# main.net
KiCad netlist of a schematic drawn in EAGLE
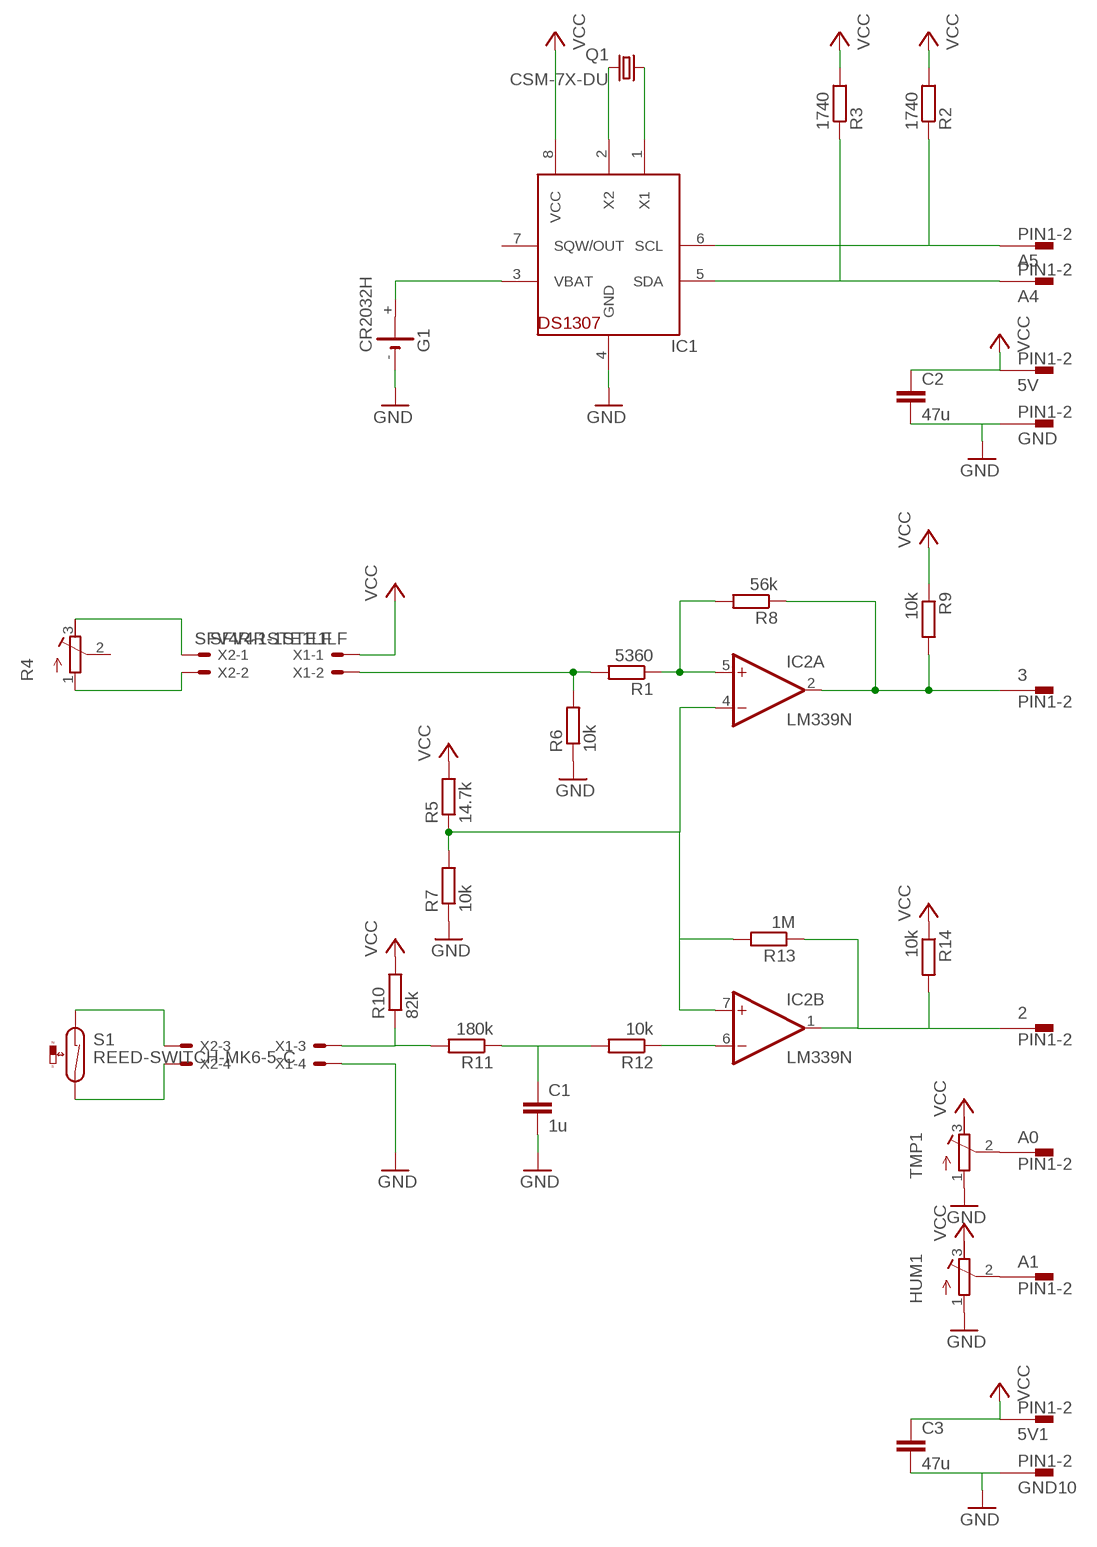
[diagram p0: schematic, sheet 1]

(export (version "E")
  (design (tool "Eeschema 10.0.6"))
  (components
    (comp (ref "2")
      (value "PIN1-2")
      (footprint "eagle-import:62221")
      (fields (field (name "MF") "TYCO ELECTRONICS") (field (name "MPN") "62221-1"))
      (libsource (lib "eagle-import") (part "PIN1-2"))
    )
    (comp (ref "3")
      (value "PIN1-2")
      (footprint "eagle-import:62221")
      (fields (field (name "MF") "TYCO ELECTRONICS") (field (name "MPN") "62221-1"))
      (libsource (lib "eagle-import") (part "PIN1-2"))
    )
    (comp (ref "5V")
      (value "PIN1-2")
      (footprint "eagle-import:62221")
      (fields (field (name "MF") "TYCO ELECTRONICS") (field (name "MPN") "62221-1"))
      (libsource (lib "eagle-import") (part "PIN1-2"))
    )
    (comp (ref "5V1")
      (value "PIN1-2")
      (footprint "eagle-import:62221")
      (fields (field (name "MF") "TYCO ELECTRONICS") (field (name "MPN") "62221-1"))
      (libsource (lib "eagle-import") (part "PIN1-2"))
    )
    (comp (ref "A0")
      (value "PIN1-2")
      (footprint "eagle-import:62221")
      (fields (field (name "MF") "TYCO ELECTRONICS") (field (name "MPN") "62221-1"))
      (libsource (lib "eagle-import") (part "PIN1-2"))
    )
    (comp (ref "A1")
      (value "PIN1-2")
      (footprint "eagle-import:62221")
      (fields (field (name "MF") "TYCO ELECTRONICS") (field (name "MPN") "62221-1"))
      (libsource (lib "eagle-import") (part "PIN1-2"))
    )
    (comp (ref "A4")
      (value "PIN1-2")
      (footprint "eagle-import:62221")
      (fields (field (name "MF") "TYCO ELECTRONICS") (field (name "MPN") "62221-1"))
      (libsource (lib "eagle-import") (part "PIN1-2"))
    )
    (comp (ref "A5")
      (value "PIN1-2")
      (footprint "eagle-import:62221")
      (fields (field (name "MF") "TYCO ELECTRONICS") (field (name "MPN") "62221-1"))
      (libsource (lib "eagle-import") (part "PIN1-2"))
    )
    (comp (ref "C1")
      (value "1u")
      (footprint "eagle-import:C2.5-3")
      (libsource (lib "eagle-import") (part "C2,5-3"))
    )
    (comp (ref "C2")
      (value "47u")
      (footprint "eagle-import:C2.5-3")
      (libsource (lib "eagle-import") (part "C2,5-3"))
    )
    (comp (ref "C3")
      (value "47u")
      (footprint "eagle-import:C2.5-3")
      (libsource (lib "eagle-import") (part "C2,5-3"))
    )
    (comp (ref "G1")
      (value "CR2032H")
      (footprint "eagle-import:CR2032H")
      (libsource (lib "eagle-import") (part "CR2032H"))
    )
    (comp (ref "GND")
      (value "PIN1-2")
      (footprint "eagle-import:62221")
      (fields (field (name "MF") "TYCO ELECTRONICS") (field (name "MPN") "62221-1"))
      (libsource (lib "eagle-import") (part "PIN1-2"))
    )
    (comp (ref "GND10")
      (value "PIN1-2")
      (footprint "eagle-import:62221")
      (fields (field (name "MF") "TYCO ELECTRONICS") (field (name "MPN") "62221-1"))
      (libsource (lib "eagle-import") (part "PIN1-2"))
    )
    (comp (ref "HUM1")
      (value "R-TRIMM4G/J")
      (footprint "eagle-import:RTRIM4G_J")
      (libsource (lib "eagle-import") (part "R-TRIMM4G/J"))
    )
    (comp (ref "IC1")
      (value "DS1307")
      (footprint "eagle-import:DIL08")
      (libsource (lib "eagle-import") (part "DS1307"))
    )
    (comp (ref "IC2")
      (value "LM339N")
      (footprint "eagle-import:DIL14")
      (libsource (lib "eagle-import") (part "LM339N"))
    )
    (comp (ref "Q1")
      (value "CSM-7X-DU")
      (footprint "eagle-import:CSM-7X-DU")
      (libsource (lib "eagle-import") (part "CSM-7X-DU"))
    )
    (comp (ref "R1")
      (value "5360")
      (footprint "eagle-import:0204V")
      (libsource (lib "eagle-import") (part "R-EU_0204/2V"))
    )
    (comp (ref "R2")
      (value "1740")
      (footprint "eagle-import:0204V")
      (libsource (lib "eagle-import") (part "R-EU_0204/2V"))
    )
    (comp (ref "R3")
      (value "1740")
      (footprint "eagle-import:0204V")
      (libsource (lib "eagle-import") (part "R-EU_0204/2V"))
    )
    (comp (ref "R4")
      (value "R-TRIMM4G/J")
      (footprint "eagle-import:RTRIM4G_J")
      (libsource (lib "eagle-import") (part "R-TRIMM4G/J"))
    )
    (comp (ref "R5")
      (value "14.7k")
      (footprint "eagle-import:0204V")
      (libsource (lib "eagle-import") (part "R-EU_0204/2V"))
    )
    (comp (ref "R6")
      (value "10k")
      (footprint "eagle-import:0204V")
      (libsource (lib "eagle-import") (part "R-EU_0204/2V"))
    )
    (comp (ref "R7")
      (value "10k")
      (footprint "eagle-import:0204V")
      (libsource (lib "eagle-import") (part "R-EU_0204/2V"))
    )
    (comp (ref "R8")
      (value "56k")
      (footprint "eagle-import:0204V")
      (libsource (lib "eagle-import") (part "R-EU_0204/2V"))
    )
    (comp (ref "R9")
      (value "10k")
      (footprint "eagle-import:0204V")
      (libsource (lib "eagle-import") (part "R-EU_0204/2V"))
    )
    (comp (ref "R10")
      (value "82k")
      (footprint "eagle-import:0204V")
      (libsource (lib "eagle-import") (part "R-EU_0204/2V"))
    )
    (comp (ref "R11")
      (value "180k")
      (footprint "eagle-import:0204V")
      (libsource (lib "eagle-import") (part "R-EU_0204/2V"))
    )
    (comp (ref "R12")
      (value "10k")
      (footprint "eagle-import:0204V")
      (libsource (lib "eagle-import") (part "R-EU_0204/2V"))
    )
    (comp (ref "R13")
      (value "1M")
      (footprint "eagle-import:0204V")
      (libsource (lib "eagle-import") (part "R-EU_0204/2V"))
    )
    (comp (ref "R14")
      (value "10k")
      (footprint "eagle-import:0204V")
      (libsource (lib "eagle-import") (part "R-EU_0204/2V"))
    )
    (comp (ref "S1")
      (value "REED-SWITCH-MK6-5-C")
      (footprint "eagle-import:MK6-5")
      (fields (field (name "MF") "MEDER") (field (name "MPN") "MK6-5-C"))
      (libsource (lib "eagle-import") (part "REED-SWITCH-MK6-5-C"))
    )
    (comp (ref "TMP1")
      (value "R-TRIMM4G/J")
      (footprint "eagle-import:RTRIM4G_J")
      (libsource (lib "eagle-import") (part "R-TRIMM4G/J"))
    )
    (comp (ref "X1")
      (value "SFV4R-1STE1LF")
      (footprint "eagle-import:SFV4R-1STE1LF")
      (libsource (lib "eagle-import") (part "SFV4R-1STE1LF"))
    )
    (comp (ref "X2")
      (value "SFV4R-1STE1LF")
      (footprint "eagle-import:SFV4R-1STE1LF")
      (libsource (lib "eagle-import") (part "SFV4R-1STE1LF"))
    )
  )
  (nets
    (net (code "1") (name "GND") (class "Default")
      (node (ref "C1") (pin "2") (pinfunction "2_2") (pintype "passive"))
      (node (ref "C2") (pin "2") (pinfunction "2_2") (pintype "passive"))
      (node (ref "C3") (pin "2") (pinfunction "2_2") (pintype "passive"))
      (node (ref "G1") (pin "-") (pinfunction "-_-") (pintype "passive"))
      (node (ref "GND") (pin "1") (pinfunction "1_1") (pintype "passive"))
      (node (ref "GND10") (pin "1") (pinfunction "1_1") (pintype "passive"))
      (node (ref "HUM1") (pin "1") (pinfunction "A_1") (pintype "passive"))
      (node (ref "IC1") (pin "4") (pinfunction "GND_4") (pintype "power_in"))
      (node (ref "R6") (pin "1") (pinfunction "1_1") (pintype "passive"))
      (node (ref "R7") (pin "1") (pinfunction "1_1") (pintype "passive"))
      (node (ref "TMP1") (pin "1") (pinfunction "A_1") (pintype "passive"))
      (node (ref "X1") (pin "4") (pinfunction "S_4") (pintype "passive"))
    )
    (net (code "2") (name "Net-(C1-Pad1)") (class "Default")
      (node (ref "C1") (pin "1") (pinfunction "1_1") (pintype "passive"))
      (node (ref "R11") (pin "1") (pinfunction "1_1") (pintype "passive"))
      (node (ref "R12") (pin "2") (pinfunction "2_2") (pintype "passive"))
    )
    (net (code "3") (name "Net-(HUM1-S)") (class "Default")
      (node (ref "A1") (pin "1") (pinfunction "1_1") (pintype "passive"))
      (node (ref "HUM1") (pin "2") (pinfunction "S_2") (pintype "passive"))
    )
    (net (code "4") (name "Net-(IC1-SCL)") (class "Default")
      (node (ref "A5") (pin "1") (pinfunction "1_1") (pintype "passive"))
      (node (ref "IC1") (pin "6") (pinfunction "SCL_6") (pintype "bidirectional"))
      (node (ref "R2") (pin "1") (pinfunction "1_1") (pintype "passive"))
    )
    (net (code "5") (name "Net-(IC1-SDA)") (class "Default")
      (node (ref "A4") (pin "1") (pinfunction "1_1") (pintype "passive"))
      (node (ref "IC1") (pin "5") (pinfunction "SDA_5") (pintype "bidirectional"))
      (node (ref "R3") (pin "1") (pinfunction "1_1") (pintype "passive"))
    )
    (net (code "6") (name "Net-(IC1-VBAT)") (class "Default")
      (node (ref "G1") (pin "+") (pinfunction "+_+") (pintype "passive"))
      (node (ref "IC1") (pin "3") (pinfunction "VBAT_3") (pintype "power_in"))
    )
    (net (code "7") (name "Net-(IC1-X1)") (class "Default")
      (node (ref "IC1") (pin "1") (pinfunction "X1_1") (pintype "passive"))
      (node (ref "Q1") (pin "1") (pinfunction "1_1") (pintype "passive"))
    )
    (net (code "8") (name "Net-(IC1-X2)") (class "Default")
      (node (ref "IC1") (pin "2") (pinfunction "X2_2") (pintype "passive"))
      (node (ref "Q1") (pin "2") (pinfunction "2_2") (pintype "passive"))
    )
    (net (code "9") (name "Net-(IC2A-+IN)") (class "Default")
      (node (ref "IC2") (pin "5") (pinfunction "+IN_5") (pintype "input"))
      (node (ref "R1") (pin "1") (pinfunction "1_1") (pintype "passive"))
      (node (ref "R8") (pin "2") (pinfunction "2_2") (pintype "passive"))
    )
    (net (code "10") (name "Net-(IC2A--IN)") (class "Default")
      (node (ref "IC2") (pin "4") (pinfunction "-IN_4") (pintype "input"))
      (node (ref "IC2") (pin "7") (pinfunction "+IN_7") (pintype "input"))
      (node (ref "R13") (pin "2") (pinfunction "2_2") (pintype "passive"))
      (node (ref "R5") (pin "1") (pinfunction "1_1") (pintype "passive"))
      (node (ref "R7") (pin "2") (pinfunction "2_2") (pintype "passive"))
    )
    (net (code "11") (name "Net-(IC2A-OUT)") (class "Default")
      (node (ref "3") (pin "1") (pinfunction "1_1") (pintype "passive"))
      (node (ref "IC2") (pin "2") (pinfunction "OUT_2") (pintype "open_collector"))
      (node (ref "R8") (pin "1") (pinfunction "1_1") (pintype "passive"))
      (node (ref "R9") (pin "2") (pinfunction "2_2") (pintype "passive"))
    )
    (net (code "12") (name "Net-(IC2B--IN)") (class "Default")
      (node (ref "IC2") (pin "6") (pinfunction "-IN_6") (pintype "input"))
      (node (ref "R12") (pin "1") (pinfunction "1_1") (pintype "passive"))
    )
    (net (code "13") (name "Net-(IC2B-OUT)") (class "Default")
      (node (ref "2") (pin "1") (pinfunction "1_1") (pintype "passive"))
      (node (ref "IC2") (pin "1") (pinfunction "OUT_1") (pintype "open_collector"))
      (node (ref "R13") (pin "1") (pinfunction "1_1") (pintype "passive"))
      (node (ref "R14") (pin "2") (pinfunction "2_2") (pintype "passive"))
    )
    (net (code "14") (name "Net-(R4-A)") (class "Default")
      (node (ref "R4") (pin "1") (pinfunction "A_1") (pintype "passive"))
      (node (ref "X2") (pin "2") (pinfunction "S_2") (pintype "passive"))
    )
    (net (code "15") (name "Net-(R4-E)") (class "Default")
      (node (ref "R4") (pin "3") (pinfunction "E_3") (pintype "passive"))
      (node (ref "X2") (pin "1") (pinfunction "S_1") (pintype "passive"))
    )
    (net (code "16") (name "Net-(TMP1-S)") (class "Default")
      (node (ref "A0") (pin "1") (pinfunction "1_1") (pintype "passive"))
      (node (ref "TMP1") (pin "2") (pinfunction "S_2") (pintype "passive"))
    )
    (net (code "17") (name "Net-(X1B-S)") (class "Default")
      (node (ref "R1") (pin "2") (pinfunction "2_2") (pintype "passive"))
      (node (ref "R6") (pin "2") (pinfunction "2_2") (pintype "passive"))
      (node (ref "X1") (pin "2") (pinfunction "S_2") (pintype "passive"))
    )
    (net (code "18") (name "Net-(X1C-S)") (class "Default")
      (node (ref "R10") (pin "1") (pinfunction "1_1") (pintype "passive"))
      (node (ref "R11") (pin "2") (pinfunction "2_2") (pintype "passive"))
      (node (ref "X1") (pin "3") (pinfunction "S_3") (pintype "passive"))
    )
    (net (code "19") (name "Net-(X2C-S)") (class "Default")
      (node (ref "S1") (pin "1") (pinfunction "1_1") (pintype "passive"))
      (node (ref "X2") (pin "3") (pinfunction "S_3") (pintype "passive"))
    )
    (net (code "20") (name "Net-(X2D-S)") (class "Default")
      (node (ref "S1") (pin "2") (pinfunction "2_2") (pintype "passive"))
      (node (ref "X2") (pin "4") (pinfunction "S_4") (pintype "passive"))
    )
    (net (code "21") (name "VCC") (class "Default")
      (node (ref "5V") (pin "1") (pinfunction "1_1") (pintype "passive"))
      (node (ref "5V1") (pin "1") (pinfunction "1_1") (pintype "passive"))
      (node (ref "C2") (pin "1") (pinfunction "1_1") (pintype "passive"))
      (node (ref "C3") (pin "1") (pinfunction "1_1") (pintype "passive"))
      (node (ref "HUM1") (pin "3") (pinfunction "E_3") (pintype "passive"))
      (node (ref "IC1") (pin "8") (pinfunction "VCC_8") (pintype "power_in"))
      (node (ref "R10") (pin "2") (pinfunction "2_2") (pintype "passive"))
      (node (ref "R14") (pin "1") (pinfunction "1_1") (pintype "passive"))
      (node (ref "R2") (pin "2") (pinfunction "2_2") (pintype "passive"))
      (node (ref "R3") (pin "2") (pinfunction "2_2") (pintype "passive"))
      (node (ref "R5") (pin "2") (pinfunction "2_2") (pintype "passive"))
      (node (ref "R9") (pin "1") (pinfunction "1_1") (pintype "passive"))
      (node (ref "TMP1") (pin "3") (pinfunction "E_3") (pintype "passive"))
      (node (ref "X1") (pin "1") (pinfunction "S_1") (pintype "passive"))
    )
    (net (code "22") (name "unconnected-(G1-+-Pad+@1)") (class "Default")
      (node (ref "G1") (pin "+@1") (pinfunction "+_+@1") (pintype "passive"))
    )
    (net (code "23") (name "unconnected-(IC1-SQW{slash}OUT-Pad7)") (class "Default")
      (node (ref "IC1") (pin "7") (pinfunction "SQW/OUT_7") (pintype "bidirectional"))
    )
    (net (code "24") (name "unconnected-(R4-S-Pad2)") (class "Default")
      (node (ref "R4") (pin "2") (pinfunction "S_2") (pintype "passive"))
    )
  )
)
